# ADC.net
KiCad netlist of a schematic drawn in Altium Designer
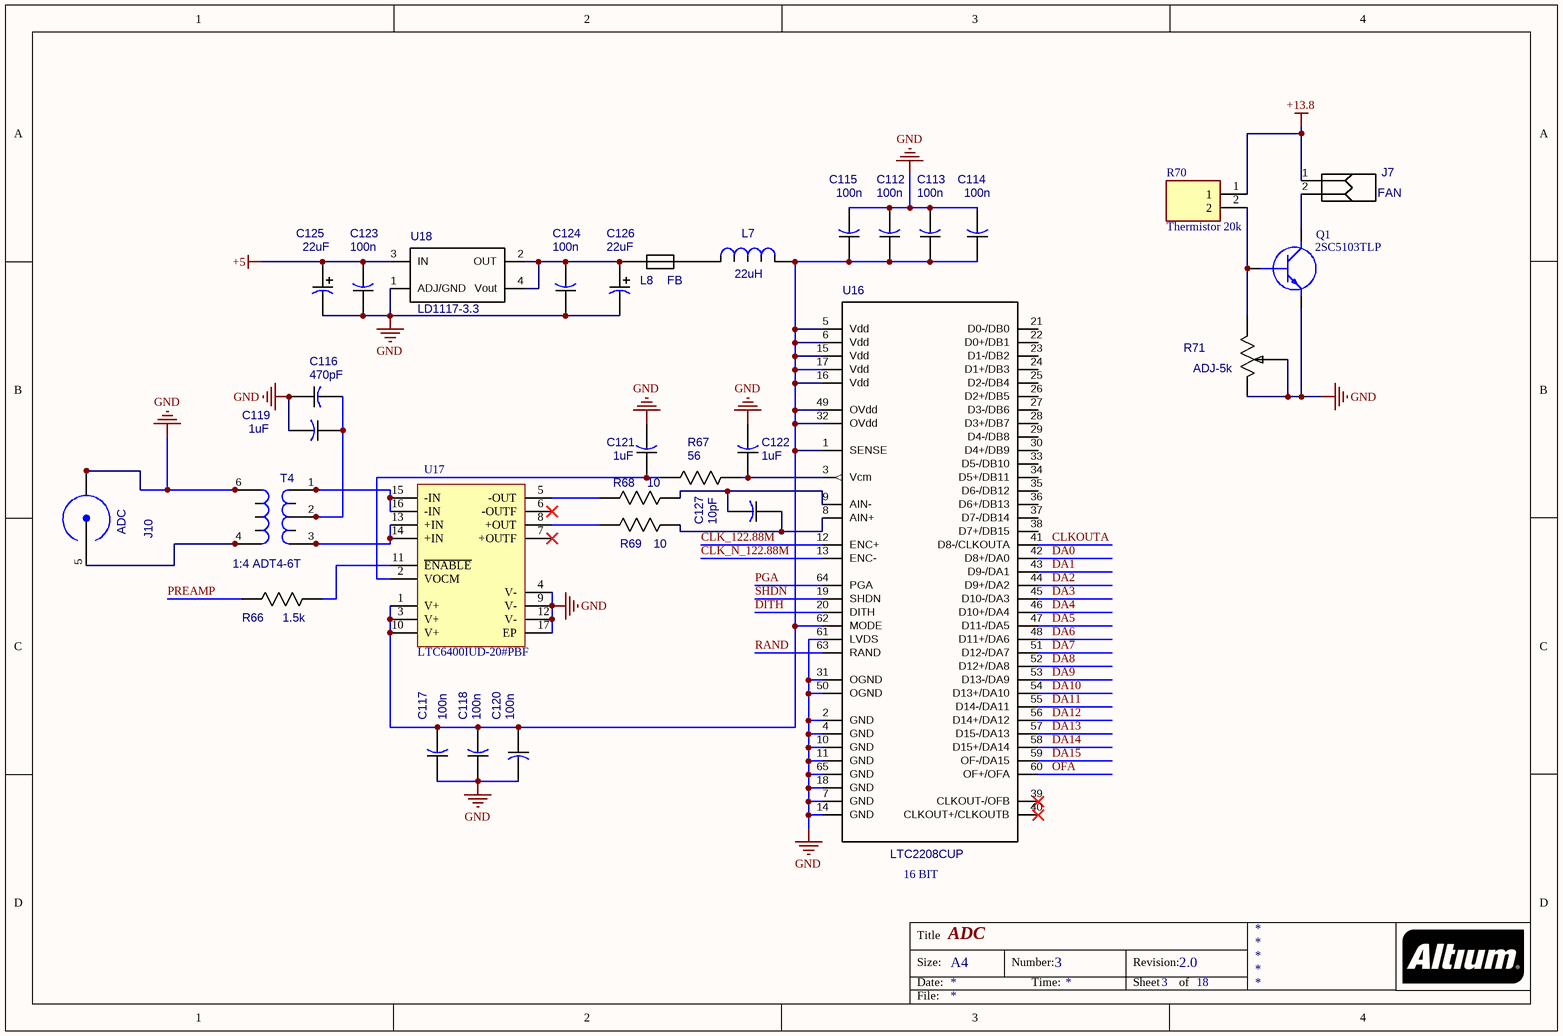
[diagram p0: ADC.SchDoc]

(export (version "E")
  (design (tool "Eeschema 10.0.6"))
  (components
    (comp (ref "C112")
      (value "100n")
      (footprint "CAP_0805")
      (description "CAP_0805")
      (libsource (lib "*") (part "CAP_0805"))
    )
    (comp (ref "C113")
      (value "100n")
      (footprint "CAP_0805")
      (description "CAP_0805")
      (libsource (lib "*") (part "CAP_0805"))
    )
    (comp (ref "C114")
      (value "100n")
      (footprint "CAP_0805")
      (description "CAP_0805")
      (libsource (lib "*") (part "CAP_0805"))
    )
    (comp (ref "C115")
      (value "100n")
      (footprint "CAP_0805")
      (description "CAP_0805")
      (libsource (lib "*") (part "CAP_0805"))
    )
    (comp (ref "C116")
      (value "470pF")
      (footprint "CAP_0805")
      (description "CAP_0805")
      (libsource (lib "*") (part "CAP_0805"))
    )
    (comp (ref "C117")
      (value "100n")
      (footprint "CAP_0805")
      (description "CAP_0805")
      (libsource (lib "*") (part "CAP_0805"))
    )
    (comp (ref "C118")
      (value "100n")
      (footprint "CAP_0805")
      (description "CAP_0805")
      (libsource (lib "*") (part "CAP_0805"))
    )
    (comp (ref "C119")
      (value "1uF")
      (footprint "CAP_0805")
      (description "CAP_0805")
      (libsource (lib "*") (part "CAP_0805"))
    )
    (comp (ref "C120")
      (value "100n")
      (footprint "CAP_0805")
      (description "CAP_0805")
      (libsource (lib "*") (part "CAP_0805"))
    )
    (comp (ref "C121")
      (value "1uF")
      (footprint "CAP_0805")
      (description "CAP_0805")
      (libsource (lib "*") (part "CAP_0805"))
    )
    (comp (ref "C122")
      (value "1uF")
      (footprint "CAP_0805")
      (description "CAP_0805")
      (libsource (lib "*") (part "CAP_0805"))
    )
    (comp (ref "C123")
      (value "100n")
      (footprint "CAP_0805")
      (description "CAP_0805")
      (libsource (lib "*") (part "CAP_0805"))
    )
    (comp (ref "C124")
      (value "100n")
      (footprint "CAP_0805")
      (description "CAP_0805")
      (libsource (lib "*") (part "CAP_0805"))
    )
    (comp (ref "C125") (value "22uF") (footprint "TC3528-1411") (libsource (lib "*") (part "EEEFC_sizeB")))
    (comp (ref "C126")
      (value "22uF")
      (footprint "TC3528-1411")
      (description "EEEFC_sizeB")
      (libsource (lib "*") (part "EEEFC_sizeB"))
    )
    (comp (ref "C127")
      (value "10pF")
      (footprint "CAP_0805")
      (description "CAP_0805")
      (libsource (lib "*") (part "CAP_0805"))
    )
    (comp (ref "J7")
      (value "FAN")
      (footprint "51022-0200")
      (description "51022-0200")
      (libsource (lib "*") (part "51022-0200"))
    )
    (comp (ref "J10")
      (value "ADC")
      (footprint "31-5431")
      (description "SMA")
      (libsource (lib "RF-UNIT_1") (part "31-5431"))
    )
    (comp (ref "L7")
      (value "22uH")
      (footprint "14-1210")
      (description "IND_1206")
      (libsource (lib "*") (part "IND_1206"))
    )
    (comp (ref "L8")
      (value "FB")
      (footprint "IND_FERRITE_BEAD")
      (description "Ferrite bead on conductor")
      (libsource (lib "MOTHERBOARD_1") (part "IND_FERRITE_BEAD"))
    )
    (comp (ref "Q1")
      (value "2SC5103TLP")
      (footprint "SamacSys:2SC5103TLQ")
      (description "Transistor BJT NPN")
      (fields (field (name "MOUSER PART NUMBER") "755-2SC5103TLP"))
      (libsource (lib "*") (part "2SC5103TLP"))
    )
    (comp (ref "R66")
      (value "1.5k")
      (footprint "RES_0805")
      (description "RES_0805")
      (libsource (lib "*") (part "RES_0805"))
    )
    (comp (ref "R67")
      (value "56")
      (footprint "RES_0805")
      (description "RES_0805")
      (libsource (lib "") (part "RES_0805_1"))
    )
    (comp (ref "R68")
      (value "10")
      (footprint "RES_0603")
      (description "RES_0603")
      (libsource (lib "*") (part "RES_0603"))
    )
    (comp (ref "R69")
      (value "10")
      (footprint "RES_0603")
      (description "RES_0603")
      (libsource (lib "*") (part "RES_0603"))
    )
    (comp (ref "R70")
      (value "Thermistor 20k")
      (footprint "MF52A103F3950A1")
      (description "Thermistor")
      (fields (field (name "MANUFACTURER_PART_NUMBER") "MF52A103F3950(A1)"))
      (libsource (lib "*") (part "MF52A103F3950_A1_"))
    )
    (comp (ref "R71")
      (value "ADJ-5k")
      (footprint "306J")
      (description "306J")
      (libsource (lib "*") (part "306J"))
    )
    (comp (ref "T4")
      (value "1:4 ADT4-6T")
      (footprint "TRANSF_ACORE2")
      (description "Transformer")
      (libsource (lib "MOTHERBOARD_1") (part "TRANSF_ACORE2"))
    )
    (comp (ref "U16") (value "LTC2208CUP") (footprint "LTC2208CUP") (libsource (lib "*") (part "LTC2208CUP")))
    (comp (ref "U17")
      (value "LTC6400IUD-20#PBF")
      (footprint "LT-UD-16_N")
      (fields
        (field (name "MANUFACTURER") "Linear Technology")
        (field (name "LINEAR TECHNOLOGY PART NUMBER") "LTC6400-20")
      )
      (libsource (lib "Altium Content Vault") (part "LT-LTC640X-X-16"))
    )
    (comp (ref "U18")
      (value "LD1117-3.3")
      (footprint "LT1117CST-3.3")
      (description "LT1117CST-3.3")
      (libsource (lib "*") (part "LT1117CST-3.3"))
    )
  )
  (nets
    (net (code "1") (name "+5") (class "Default")
      (node (ref "C123") (pin "2") (pinfunction "2_2") (pintype "passive"))
      (node (ref "C125") (pin "1") (pinfunction "PLUS_1") (pintype "passive"))
      (node (ref "U18") (pin "3") (pinfunction "IN_3") (pintype "passive"))
    )
    (net (code "2") (name "+13.8") (class "Default")
      (node (ref "J7") (pin "1") (pinfunction "1_1") (pintype "passive"))
      (node (ref "R70") (pin "1") (pinfunction "1_1") (pintype "passive"))
    )
    (net (code "3") (name "/CLKOUTA") (class "Default")
      (node (ref "U16") (pin "41") (pinfunction "D8-/CLKOUTA_41") (pintype "passive"))
    )
    (net (code "4") (name "/CLK_122.88M") (class "Default")
      (node (ref "U16") (pin "12") (pinfunction "ENC+_12") (pintype "passive"))
    )
    (net (code "5") (name "/CLK_N_122.88M") (class "Default")
      (node (ref "U16") (pin "13") (pinfunction "ENC-_13") (pintype "passive"))
    )
    (net (code "6") (name "/DA0") (class "Default")
      (node (ref "U16") (pin "42") (pinfunction "D8+/DA0_42") (pintype "passive"))
    )
    (net (code "7") (name "/DA1") (class "Default")
      (node (ref "U16") (pin "43") (pinfunction "D9-/DA1_43") (pintype "passive"))
    )
    (net (code "8") (name "/DA2") (class "Default")
      (node (ref "U16") (pin "44") (pinfunction "D9+/DA2_44") (pintype "passive"))
    )
    (net (code "9") (name "/DA3") (class "Default")
      (node (ref "U16") (pin "45") (pinfunction "D10-/DA3_45") (pintype "passive"))
    )
    (net (code "10") (name "/DA4") (class "Default")
      (node (ref "U16") (pin "46") (pinfunction "D10+/DA4_46") (pintype "passive"))
    )
    (net (code "11") (name "/DA5") (class "Default")
      (node (ref "U16") (pin "47") (pinfunction "D11-/DA5_47") (pintype "passive"))
    )
    (net (code "12") (name "/DA6") (class "Default")
      (node (ref "U16") (pin "48") (pinfunction "D11+/DA6_48") (pintype "passive"))
    )
    (net (code "13") (name "/DA7") (class "Default")
      (node (ref "U16") (pin "51") (pinfunction "D12-/DA7_51") (pintype "passive"))
    )
    (net (code "14") (name "/DA8") (class "Default")
      (node (ref "U16") (pin "52") (pinfunction "D12+/DA8_52") (pintype "passive"))
    )
    (net (code "15") (name "/DA9") (class "Default")
      (node (ref "U16") (pin "53") (pinfunction "D13-/DA9_53") (pintype "passive"))
    )
    (net (code "16") (name "/DA10") (class "Default")
      (node (ref "U16") (pin "54") (pinfunction "D13+/DA10_54") (pintype "passive"))
    )
    (net (code "17") (name "/DA11") (class "Default")
      (node (ref "U16") (pin "55") (pinfunction "D14-/DA11_55") (pintype "passive"))
    )
    (net (code "18") (name "/DA12") (class "Default")
      (node (ref "U16") (pin "56") (pinfunction "D14+/DA12_56") (pintype "passive"))
    )
    (net (code "19") (name "/DA13") (class "Default")
      (node (ref "U16") (pin "57") (pinfunction "D15-/DA13_57") (pintype "passive"))
    )
    (net (code "20") (name "/DA14") (class "Default")
      (node (ref "U16") (pin "58") (pinfunction "D15+/DA14_58") (pintype "passive"))
    )
    (net (code "21") (name "/DA15") (class "Default")
      (node (ref "U16") (pin "59") (pinfunction "OF-/DA15_59") (pintype "passive"))
    )
    (net (code "22") (name "/DITH") (class "Default")
      (node (ref "U16") (pin "20") (pinfunction "DITH_20") (pintype "passive"))
    )
    (net (code "23") (name "/OFA") (class "Default")
      (node (ref "U16") (pin "60") (pinfunction "OF+/OFA_60") (pintype "passive"))
    )
    (net (code "24") (name "/PGA") (class "Default")
      (node (ref "U16") (pin "64") (pinfunction "PGA_64") (pintype "passive"))
    )
    (net (code "25") (name "/PREAMP") (class "Default")
      (node (ref "R66") (pin "2") (pinfunction "1_2") (pintype "passive"))
    )
    (net (code "26") (name "/RAND") (class "Default")
      (node (ref "U16") (pin "63") (pinfunction "RAND_63") (pintype "passive"))
    )
    (net (code "27") (name "/SHDN") (class "Default")
      (node (ref "U16") (pin "19") (pinfunction "SHDN_19") (pintype "passive"))
    )
    (net (code "28") (name "GND") (class "Default")
      (node (ref "C112") (pin "2") (pinfunction "2_2") (pintype "passive"))
      (node (ref "C113") (pin "2") (pinfunction "2_2") (pintype "passive"))
      (node (ref "C114") (pin "2") (pinfunction "2_2") (pintype "passive"))
      (node (ref "C115") (pin "2") (pinfunction "2_2") (pintype "passive"))
      (node (ref "C116") (pin "1") (pinfunction "1_1") (pintype "passive"))
      (node (ref "C117") (pin "1") (pinfunction "1_1") (pintype "passive"))
      (node (ref "C118") (pin "1") (pinfunction "1_1") (pintype "passive"))
      (node (ref "C119") (pin "2") (pinfunction "2_2") (pintype "passive"))
      (node (ref "C120") (pin "2") (pinfunction "2_2") (pintype "passive"))
      (node (ref "C121") (pin "2") (pinfunction "2_2") (pintype "passive"))
      (node (ref "C122") (pin "2") (pinfunction "2_2") (pintype "passive"))
      (node (ref "C123") (pin "1") (pinfunction "1_1") (pintype "passive"))
      (node (ref "C124") (pin "1") (pinfunction "1_1") (pintype "passive"))
      (node (ref "C125") (pin "2") (pinfunction "MINUS_2") (pintype "passive"))
      (node (ref "C126") (pin "2") (pinfunction "MINUS_2") (pintype "passive"))
      (node (ref "J10") (pin "1") (pinfunction "GND_1") (pintype "passive"))
      (node (ref "J10") (pin "2") (pinfunction "GND_2") (pintype "passive"))
      (node (ref "J10") (pin "3") (pinfunction "GND_3") (pintype "passive"))
      (node (ref "J10") (pin "4") (pinfunction "GND_4") (pintype "passive"))
      (node (ref "Q1") (pin "3") (pinfunction "E_3") (pintype "passive"))
      (node (ref "R71") (pin "1") (pinfunction "CCW_1") (pintype "passive"))
      (node (ref "R71") (pin "2") (pinfunction "W_2") (pintype "passive"))
      (node (ref "T4") (pin "10") (pinfunction "0_10") (pintype "passive"))
      (node (ref "T4") (pin "6") (pinfunction "P2_6") (pintype "passive"))
      (node (ref "U16") (pin "10") (pinfunction "GND_10") (pintype "passive"))
      (node (ref "U16") (pin "11") (pinfunction "GND_11") (pintype "passive"))
      (node (ref "U16") (pin "14") (pinfunction "GND_14") (pintype "passive"))
      (node (ref "U16") (pin "18") (pinfunction "GND_18") (pintype "passive"))
      (node (ref "U16") (pin "2") (pinfunction "GND_2") (pintype "passive"))
      (node (ref "U16") (pin "31") (pinfunction "OGND_31") (pintype "passive"))
      (node (ref "U16") (pin "4") (pinfunction "GND_4") (pintype "passive"))
      (node (ref "U16") (pin "50") (pinfunction "OGND_50") (pintype "passive"))
      (node (ref "U16") (pin "61") (pinfunction "LVDS_61") (pintype "passive"))
      (node (ref "U16") (pin "65") (pinfunction "GND_65") (pintype "passive"))
      (node (ref "U16") (pin "7") (pinfunction "GND_7") (pintype "passive"))
      (node (ref "U17") (pin "12") (pinfunction "V-_12") (pintype "power_in"))
      (node (ref "U17") (pin "17") (pinfunction "EP_17") (pintype "power_in"))
      (node (ref "U17") (pin "4") (pinfunction "V-_4") (pintype "power_in"))
      (node (ref "U17") (pin "9") (pinfunction "V-_9") (pintype "power_in"))
      (node (ref "U18") (pin "1") (pinfunction "ADJ/GND_1") (pintype "passive"))
    )
    (net (code "29") (name "Net-(C126-PLUS)") (class "Default")
      (node (ref "C124") (pin "2") (pinfunction "2_2") (pintype "passive"))
      (node (ref "C126") (pin "1") (pinfunction "PLUS_1") (pintype "passive"))
      (node (ref "L8") (pin "1") (pinfunction "1_1") (pintype "passive"))
      (node (ref "U18") (pin "2") (pinfunction "OUT_2") (pintype "passive"))
      (node (ref "U18") (pin "4") (pinfunction "Vout_4") (pintype "passive"))
    )
    (net (code "30") (name "Net-(J10-CON)") (class "Default")
      (node (ref "J10") (pin "5") (pinfunction "CON_5") (pintype "passive"))
      (node (ref "T4") (pin "11") (pinfunction "0_11") (pintype "passive"))
      (node (ref "T4") (pin "4") (pinfunction "P1_4") (pintype "passive"))
    )
    (net (code "31") (name "Net-(L7-Pad1)") (class "Default")
      (node (ref "L7") (pin "1") (pinfunction "1_1") (pintype "passive"))
      (node (ref "L8") (pin "2") (pinfunction "2_2") (pintype "passive"))
    )
    (net (code "32") (name "Net-(Q1-B)") (class "Default")
      (node (ref "Q1") (pin "1") (pinfunction "B_1") (pintype "passive"))
      (node (ref "R70") (pin "2") (pinfunction "2_2") (pintype "passive"))
      (node (ref "R71") (pin "3") (pinfunction "CW_3") (pintype "passive"))
    )
    (net (code "33") (name "Net-(Q1-C)") (class "Default")
      (node (ref "J7") (pin "2") (pinfunction "2_2") (pintype "passive"))
      (node (ref "Q1") (pin "2") (pinfunction "C_2") (pintype "passive"))
    )
    (net (code "34") (name "Net-(R66-2)") (class "Default")
      (node (ref "R66") (pin "1") (pinfunction "2_1") (pintype "passive"))
      (node (ref "U17") (pin "11") (pinfunction "~{ENABLE}_11") (pintype "passive"))
    )
    (net (code "35") (name "Net-(T4-S1)") (class "Default")
      (node (ref "T4") (pin "3") (pinfunction "S1_3") (pintype "passive"))
      (node (ref "T4") (pin "9") (pinfunction "0_9") (pintype "passive"))
      (node (ref "U17") (pin "13") (pinfunction "+IN_13") (pintype "passive"))
      (node (ref "U17") (pin "14") (pinfunction "+IN_14") (pintype "passive"))
    )
    (net (code "36") (name "Net-(T4-S2)") (class "Default")
      (node (ref "C116") (pin "2") (pinfunction "2_2") (pintype "passive"))
      (node (ref "C119") (pin "1") (pinfunction "1_1") (pintype "passive"))
      (node (ref "T4") (pin "2") (pinfunction "S2_2") (pintype "passive"))
      (node (ref "T4") (pin "8") (pinfunction "0_8") (pintype "passive"))
    )
    (net (code "37") (name "Net-(T4-S3)") (class "Default")
      (node (ref "T4") (pin "1") (pinfunction "S3_1") (pintype "passive"))
      (node (ref "T4") (pin "7") (pinfunction "0_7") (pintype "passive"))
      (node (ref "U17") (pin "15") (pinfunction "-IN_15") (pintype "passive"))
      (node (ref "U17") (pin "16") (pinfunction "-IN_16") (pintype "passive"))
    )
    (net (code "38") (name "Net-(U16-AIN+)") (class "Default")
      (node (ref "C127") (pin "1") (pinfunction "1_1") (pintype "passive"))
      (node (ref "R69") (pin "2") (pinfunction "2_2") (pintype "passive"))
      (node (ref "U16") (pin "8") (pinfunction "AIN+_8") (pintype "passive"))
    )
    (net (code "39") (name "Net-(U16-AIN-)") (class "Default")
      (node (ref "C127") (pin "2") (pinfunction "2_2") (pintype "passive"))
      (node (ref "R68") (pin "2") (pinfunction "2_2") (pintype "passive"))
      (node (ref "U16") (pin "9") (pinfunction "AIN-_9") (pintype "passive"))
    )
    (net (code "40") (name "Net-(U16-MODE)") (class "Default")
      (node (ref "C112") (pin "1") (pinfunction "1_1") (pintype "passive"))
      (node (ref "C113") (pin "1") (pinfunction "1_1") (pintype "passive"))
      (node (ref "C114") (pin "1") (pinfunction "1_1") (pintype "passive"))
      (node (ref "C115") (pin "1") (pinfunction "1_1") (pintype "passive"))
      (node (ref "C117") (pin "2") (pinfunction "2_2") (pintype "passive"))
      (node (ref "C118") (pin "2") (pinfunction "2_2") (pintype "passive"))
      (node (ref "C120") (pin "1") (pinfunction "1_1") (pintype "passive"))
      (node (ref "L7") (pin "2") (pinfunction "2_2") (pintype "passive"))
      (node (ref "U16") (pin "1") (pinfunction "SENSE_1") (pintype "passive"))
      (node (ref "U16") (pin "15") (pinfunction "Vdd_15") (pintype "passive"))
      (node (ref "U16") (pin "16") (pinfunction "Vdd_16") (pintype "passive"))
      (node (ref "U16") (pin "17") (pinfunction "Vdd_17") (pintype "passive"))
      (node (ref "U16") (pin "32") (pinfunction "OVdd_32") (pintype "passive"))
      (node (ref "U16") (pin "49") (pinfunction "OVdd_49") (pintype "passive"))
      (node (ref "U16") (pin "5") (pinfunction "Vdd_5") (pintype "passive"))
      (node (ref "U16") (pin "6") (pinfunction "Vdd_6") (pintype "passive"))
      (node (ref "U16") (pin "62") (pinfunction "MODE_62") (pintype "passive"))
      (node (ref "U17") (pin "1") (pinfunction "V+_1") (pintype "power_in"))
      (node (ref "U17") (pin "10") (pinfunction "V+_10") (pintype "power_in"))
      (node (ref "U17") (pin "3") (pinfunction "V+_3") (pintype "power_in"))
    )
    (net (code "41") (name "Net-(U16-Vcm)") (class "Default")
      (node (ref "C122") (pin "1") (pinfunction "1_1") (pintype "passive"))
      (node (ref "R67") (pin "2") (pinfunction "2_2") (pintype "passive"))
      (node (ref "U16") (pin "3") (pinfunction "Vcm_3") (pintype "output"))
    )
    (net (code "42") (name "Net-(U17-+OUT)") (class "Default")
      (node (ref "R69") (pin "1") (pinfunction "1_1") (pintype "passive"))
      (node (ref "U17") (pin "8") (pinfunction "+OUT_8") (pintype "passive"))
    )
    (net (code "43") (name "Net-(U17--OUT)") (class "Default")
      (node (ref "R68") (pin "1") (pinfunction "1_1") (pintype "passive"))
      (node (ref "U17") (pin "5") (pinfunction "-OUT_5") (pintype "passive"))
    )
    (net (code "44") (name "Net-(U17-VOCM)") (class "Default")
      (node (ref "C121") (pin "1") (pinfunction "1_1") (pintype "passive"))
      (node (ref "R67") (pin "1") (pinfunction "1_1") (pintype "passive"))
      (node (ref "U17") (pin "2") (pinfunction "VOCM_2") (pintype "passive"))
    )
    (net (code "45") (name "unconnected-(U16-CLKOUT+{slash}CLKOUTB-Pad40)") (class "Default")
      (node (ref "U16") (pin "40") (pinfunction "CLKOUT+/CLKOUTB_40") (pintype "passive+no_connect"))
    )
    (net (code "46") (name "unconnected-(U16-CLKOUT-{slash}OFB-Pad39)") (class "Default")
      (node (ref "U16") (pin "39") (pinfunction "CLKOUT-/OFB_39") (pintype "passive+no_connect"))
    )
    (net (code "47") (name "unconnected-(U16-D0+{slash}DB1-Pad22)") (class "Default")
      (node (ref "U16") (pin "22") (pinfunction "D0+/DB1_22") (pintype "passive"))
    )
    (net (code "48") (name "unconnected-(U16-D0-{slash}DB0-Pad21)") (class "Default")
      (node (ref "U16") (pin "21") (pinfunction "D0-/DB0_21") (pintype "passive"))
    )
    (net (code "49") (name "unconnected-(U16-D1+{slash}DB3-Pad24)") (class "Default")
      (node (ref "U16") (pin "24") (pinfunction "D1+/DB3_24") (pintype "passive"))
    )
    (net (code "50") (name "unconnected-(U16-D1-{slash}DB2-Pad23)") (class "Default")
      (node (ref "U16") (pin "23") (pinfunction "D1-/DB2_23") (pintype "passive"))
    )
    (net (code "51") (name "unconnected-(U16-D2+{slash}DB5-Pad26)") (class "Default")
      (node (ref "U16") (pin "26") (pinfunction "D2+/DB5_26") (pintype "passive"))
    )
    (net (code "52") (name "unconnected-(U16-D2-{slash}DB4-Pad25)") (class "Default")
      (node (ref "U16") (pin "25") (pinfunction "D2-/DB4_25") (pintype "passive"))
    )
    (net (code "53") (name "unconnected-(U16-D3+{slash}DB7-Pad28)") (class "Default")
      (node (ref "U16") (pin "28") (pinfunction "D3+/DB7_28") (pintype "passive"))
    )
    (net (code "54") (name "unconnected-(U16-D3-{slash}DB6-Pad27)") (class "Default")
      (node (ref "U16") (pin "27") (pinfunction "D3-/DB6_27") (pintype "passive"))
    )
    (net (code "55") (name "unconnected-(U16-D4+{slash}DB9-Pad30)") (class "Default")
      (node (ref "U16") (pin "30") (pinfunction "D4+/DB9_30") (pintype "passive"))
    )
    (net (code "56") (name "unconnected-(U16-D4-{slash}DB8-Pad29)") (class "Default")
      (node (ref "U16") (pin "29") (pinfunction "D4-/DB8_29") (pintype "passive"))
    )
    (net (code "57") (name "unconnected-(U16-D5+{slash}DB11-Pad34)") (class "Default")
      (node (ref "U16") (pin "34") (pinfunction "D5+/DB11_34") (pintype "passive"))
    )
    (net (code "58") (name "unconnected-(U16-D5-{slash}DB10-Pad33)") (class "Default")
      (node (ref "U16") (pin "33") (pinfunction "D5-/DB10_33") (pintype "passive"))
    )
    (net (code "59") (name "unconnected-(U16-D6+{slash}DB13-Pad36)") (class "Default")
      (node (ref "U16") (pin "36") (pinfunction "D6+/DB13_36") (pintype "passive"))
    )
    (net (code "60") (name "unconnected-(U16-D6-{slash}DB12-Pad35)") (class "Default")
      (node (ref "U16") (pin "35") (pinfunction "D6-/DB12_35") (pintype "passive"))
    )
    (net (code "61") (name "unconnected-(U16-D7+{slash}DB15-Pad38)") (class "Default")
      (node (ref "U16") (pin "38") (pinfunction "D7+/DB15_38") (pintype "passive"))
    )
    (net (code "62") (name "unconnected-(U16-D7-{slash}DB14-Pad37)") (class "Default")
      (node (ref "U16") (pin "37") (pinfunction "D7-/DB14_37") (pintype "passive"))
    )
    (net (code "63") (name "unconnected-(U17-+OUTF-Pad7)") (class "Default")
      (node (ref "U17") (pin "7") (pinfunction "+OUTF_7") (pintype "passive+no_connect"))
    )
    (net (code "64") (name "unconnected-(U17--OUTF-Pad6)") (class "Default")
      (node (ref "U17") (pin "6") (pinfunction "-OUTF_6") (pintype "passive+no_connect"))
    )
  )
)
